# 18_PWR_INPUT.net
KiCad netlist of a schematic drawn in Altium Designer
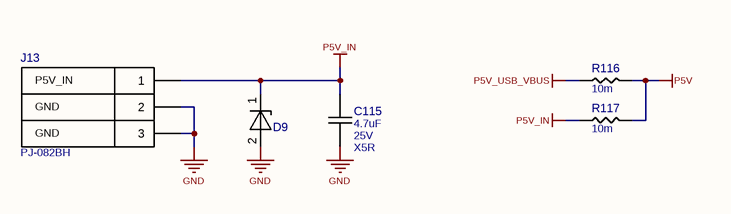
[diagram p0: 18_PWR_INPUT.SchDoc]

(export (version "E")
  (design (tool "Eeschema 10.0.6"))
  (components
    (comp (ref "C115")
      (value "4.7uF")
      (footprint "CAPC1608X08N")
      (description "CAP CER 4.7UF 25V X5R 0603")
      (fields
        (field (name "PART NUMBER") "GRM188R61E475KE11D")
        (field (name "VOLTAGE") "25V")
        (field (name "TEMPC") "X5R")
      )
      (libsource (lib "Database") (part "Capacitor"))
    )
    (comp (ref "D9")
      (value "ESD401DPYR")
      (footprint "DFN65P100X50-2N")
      (description "TVS DIODE 5.5V 24V 2X1SON")
      (libsource (lib "Database") (part "Diode Zener"))
    )
    (comp (ref "J13")
      (value "PJ-082BH")
      (footprint "CUI_PJ-082BH")
      (description "CONN PWR JACK 2.5X5.5MM SOLDER")
      (libsource (lib "Database") (part "Connector P3"))
    )
    (comp (ref "R116")
      (value "10m")
      (footprint "RESC2012X06N")
      (description "RES 0.01 OHM 1% 1/4W 0805")
      (fields (field (name "PART NUMBER") "PF0805FRM7W0R01L"))
      (libsource (lib "Database") (part "Resistor_ENG"))
    )
    (comp (ref "R117")
      (value "10m")
      (footprint "RESC2012X06N")
      (description "RES 0.01 OHM 1% 1/4W 0805")
      (fields (field (name "PART NUMBER") "PF0805FRM7W0R01L"))
      (libsource (lib "Database") (part "Resistor_ENG"))
    )
  )
  (nets
    (net (code "1") (name "GND") (class "Default")
      (node (ref "C115") (pin "1") (pinfunction "1_1") (pintype "passive"))
      (node (ref "D9") (pin "2") (pinfunction "A_2") (pintype "passive"))
      (node (ref "J13") (pin "2") (pinfunction "2_2") (pintype "passive"))
      (node (ref "J13") (pin "3") (pinfunction "3_3") (pintype "passive"))
    )
    (net (code "2") (name "P5V") (class "Default")
      (node (ref "R116") (pin "2") (pinfunction "2_2") (pintype "passive"))
      (node (ref "R117") (pin "2") (pinfunction "2_2") (pintype "passive"))
    )
    (net (code "3") (name "P5V_IN") (class "Default")
      (node (ref "C115") (pin "2") (pinfunction "2_2") (pintype "passive"))
      (node (ref "D9") (pin "1") (pinfunction "C_1") (pintype "passive"))
      (node (ref "J13") (pin "1") (pinfunction "1_1") (pintype "passive"))
      (node (ref "R117") (pin "1") (pinfunction "1_1") (pintype "passive"))
    )
    (net (code "4") (name "P5V_USB_VBUS") (class "Default")
      (node (ref "R116") (pin "1") (pinfunction "1_1") (pintype "passive"))
    )
  )
)
